# TIMER_ARDUINO_NPN.net
KiCad netlist of a schematic drawn in EAGLE
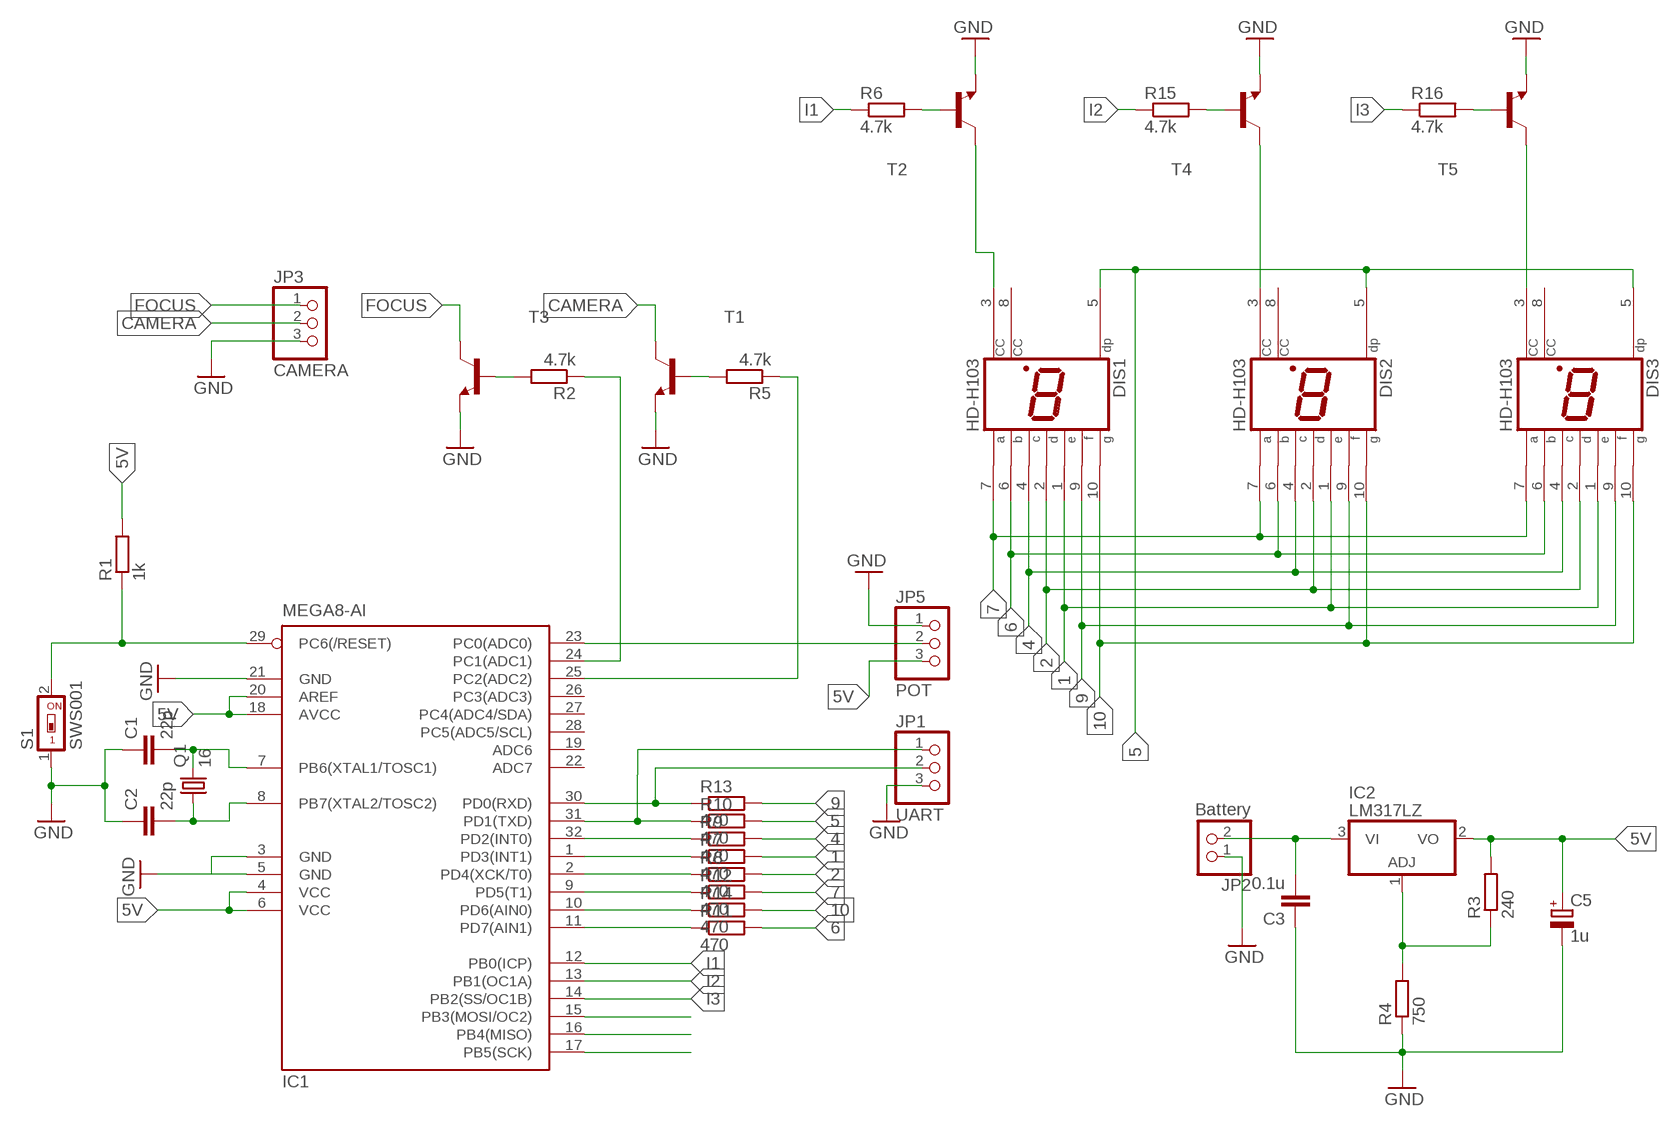
[diagram p0: schematic, sheet 1]

(export (version "E")
  (design (tool "Eeschema 10.0.6"))
  (components
    (comp (ref "C1")
      (value "22p")
      (footprint "eagle-import:C0805")
      (libsource (lib "eagle-import") (part "C-EUC0805"))
    )
    (comp (ref "C2")
      (value "22p")
      (footprint "eagle-import:C0805")
      (libsource (lib "eagle-import") (part "C-EUC0805"))
    )
    (comp (ref "C3")
      (value "0.1u")
      (footprint "eagle-import:C0805")
      (libsource (lib "eagle-import") (part "C-EUC0805"))
    )
    (comp (ref "C5")
      (value "1u")
      (footprint "eagle-import:153CLV-0405")
      (libsource (lib "eagle-import") (part "CPOL-EU153CLV-0405"))
    )
    (comp (ref "DIS1")
      (value "HD-H103")
      (footprint "eagle-import:HDSP-M")
      (libsource (lib "eagle-import") (part "HD-H103"))
    )
    (comp (ref "DIS2")
      (value "HD-H103")
      (footprint "eagle-import:HDSP-M")
      (libsource (lib "eagle-import") (part "HD-H103"))
    )
    (comp (ref "DIS3")
      (value "HD-H103")
      (footprint "eagle-import:HDSP-M")
      (libsource (lib "eagle-import") (part "HD-H103"))
    )
    (comp (ref "IC1")
      (value "MEGA8-AI")
      (footprint "eagle-import:TQFP32-08")
      (fields (field (name "MPN") "ATMEGA8-16AU"))
      (libsource (lib "eagle-import") (part "MEGA8-AI"))
    )
    (comp (ref "IC2")
      (value "LM317LZ")
      (footprint "eagle-import:TO92")
      (libsource (lib "eagle-import") (part "317LZLM"))
    )
    (comp (ref "JP1")
      (value "UART")
      (footprint "eagle-import:1X03")
      (libsource (lib "eagle-import") (part "PINHD-1X3"))
    )
    (comp (ref "JP2")
      (value "Battery")
      (footprint "eagle-import:1X02")
      (libsource (lib "eagle-import") (part "PINHD-1X2"))
    )
    (comp (ref "JP3")
      (value "CAMERA")
      (footprint "eagle-import:1X03")
      (libsource (lib "eagle-import") (part "PINHD-1X3"))
    )
    (comp (ref "JP5")
      (value "POT")
      (footprint "eagle-import:1X03")
      (libsource (lib "eagle-import") (part "PINHD-1X3"))
    )
    (comp (ref "Q1")
      (value "16")
      (footprint "eagle-import:HC33U-V")
      (libsource (lib "eagle-import") (part "CRYSTALHC33U-V"))
    )
    (comp (ref "R1")
      (value "1k")
      (footprint "eagle-import:R1206")
      (libsource (lib "eagle-import") (part "R-EU_R1206"))
    )
    (comp (ref "R2")
      (value "4.7k")
      (footprint "eagle-import:R0805")
      (libsource (lib "eagle-import") (part "R-EU_R0805"))
    )
    (comp (ref "R3")
      (value "240")
      (footprint "eagle-import:R0805")
      (libsource (lib "eagle-import") (part "R-EU_R0805"))
    )
    (comp (ref "R4")
      (value "750")
      (footprint "eagle-import:R0805")
      (libsource (lib "eagle-import") (part "R-EU_R0805"))
    )
    (comp (ref "R5")
      (value "4.7k")
      (footprint "eagle-import:R0805")
      (libsource (lib "eagle-import") (part "R-EU_R0805"))
    )
    (comp (ref "R6")
      (value "4.7k")
      (footprint "eagle-import:R0805")
      (libsource (lib "eagle-import") (part "R-EU_R0805"))
    )
    (comp (ref "R7")
      (value "470")
      (footprint "eagle-import:R0805")
      (libsource (lib "eagle-import") (part "R-EU_R0805"))
    )
    (comp (ref "R8")
      (value "470")
      (footprint "eagle-import:R0805")
      (libsource (lib "eagle-import") (part "R-EU_R0805"))
    )
    (comp (ref "R9")
      (value "470")
      (footprint "eagle-import:R0805")
      (libsource (lib "eagle-import") (part "R-EU_R0805"))
    )
    (comp (ref "R10")
      (value "470")
      (footprint "eagle-import:R0805")
      (libsource (lib "eagle-import") (part "R-EU_R0805"))
    )
    (comp (ref "R11")
      (value "470")
      (footprint "eagle-import:R0805")
      (libsource (lib "eagle-import") (part "R-EU_R0805"))
    )
    (comp (ref "R12")
      (value "470")
      (footprint "eagle-import:R0805")
      (libsource (lib "eagle-import") (part "R-EU_R0805"))
    )
    (comp (ref "R13")
      (value "470")
      (footprint "eagle-import:R0805")
      (libsource (lib "eagle-import") (part "R-EU_R0805"))
    )
    (comp (ref "R14")
      (value "470")
      (footprint "eagle-import:R0805")
      (libsource (lib "eagle-import") (part "R-EU_R0805"))
    )
    (comp (ref "R15")
      (value "4.7k")
      (footprint "eagle-import:R0805")
      (libsource (lib "eagle-import") (part "R-EU_R0805"))
    )
    (comp (ref "R16")
      (value "4.7k")
      (footprint "eagle-import:R0805")
      (libsource (lib "eagle-import") (part "R-EU_R0805"))
    )
    (comp (ref "S1")
      (value "SWS001")
      (footprint "eagle-import:SMS-001")
      (libsource (lib "eagle-import") (part "SWS001"))
    )
    (comp (ref "T1")
      (value "BC846B-NPN-SOT23-BEC")
      (footprint "eagle-import:SOT23-BEC")
      (libsource (lib "eagle-import") (part "-NPN-SOT23-BECBC846B"))
    )
    (comp (ref "T2")
      (value "BC846B-NPN-SOT23-BEC")
      (footprint "eagle-import:SOT23-BEC")
      (libsource (lib "eagle-import") (part "-NPN-SOT23-BECBC846B"))
    )
    (comp (ref "T3")
      (value "BC846B-NPN-SOT23-BEC")
      (footprint "eagle-import:SOT23-BEC")
      (libsource (lib "eagle-import") (part "-NPN-SOT23-BECBC846B"))
    )
    (comp (ref "T4")
      (value "BC846B-NPN-SOT23-BEC")
      (footprint "eagle-import:SOT23-BEC")
      (libsource (lib "eagle-import") (part "-NPN-SOT23-BECBC846B"))
    )
    (comp (ref "T5")
      (value "BC846B-NPN-SOT23-BEC")
      (footprint "eagle-import:SOT23-BEC")
      (libsource (lib "eagle-import") (part "-NPN-SOT23-BECBC846B"))
    )
  )
  (nets
    (net (code "1") (name "1") (class "Default")
      (node (ref "DIS1") (pin "1") (pinfunction "E_1") (pintype "passive"))
      (node (ref "DIS2") (pin "1") (pinfunction "E_1") (pintype "passive"))
      (node (ref "DIS3") (pin "1") (pinfunction "E_1") (pintype "passive"))
      (node (ref "R7") (pin "2") (pinfunction "2_2") (pintype "passive"))
    )
    (net (code "2") (name "2") (class "Default")
      (node (ref "DIS1") (pin "2") (pinfunction "D_2") (pintype "passive"))
      (node (ref "DIS2") (pin "2") (pinfunction "D_2") (pintype "passive"))
      (node (ref "DIS3") (pin "2") (pinfunction "D_2") (pintype "passive"))
      (node (ref "R8") (pin "2") (pinfunction "2_2") (pintype "passive"))
    )
    (net (code "3") (name "4") (class "Default")
      (node (ref "DIS1") (pin "4") (pinfunction "C_4") (pintype "passive"))
      (node (ref "DIS2") (pin "4") (pinfunction "C_4") (pintype "passive"))
      (node (ref "DIS3") (pin "4") (pinfunction "C_4") (pintype "passive"))
      (node (ref "R9") (pin "2") (pinfunction "2_2") (pintype "passive"))
    )
    (net (code "4") (name "5") (class "Default")
      (node (ref "DIS1") (pin "5") (pinfunction "DP_5") (pintype "passive"))
      (node (ref "DIS2") (pin "5") (pinfunction "DP_5") (pintype "passive"))
      (node (ref "DIS3") (pin "5") (pinfunction "DP_5") (pintype "passive"))
      (node (ref "R10") (pin "2") (pinfunction "2_2") (pintype "passive"))
    )
    (net (code "5") (name "5V") (class "Default")
      (node (ref "C5") (pin "+") (pinfunction "+_+") (pintype "passive"))
      (node (ref "IC1") (pin "18") (pinfunction "AVCC_18") (pintype "power_in"))
      (node (ref "IC1") (pin "20") (pinfunction "AREF_20") (pintype "passive"))
      (node (ref "IC1") (pin "4") (pinfunction "VCC_4") (pintype "power_in"))
      (node (ref "IC1") (pin "6") (pinfunction "VCC_6") (pintype "power_in"))
      (node (ref "IC2") (pin "2") (pinfunction "VO_2") (pintype "passive"))
      (node (ref "JP5") (pin "3") (pinfunction "3_3") (pintype "passive"))
      (node (ref "R1") (pin "2") (pinfunction "2_2") (pintype "passive"))
      (node (ref "R3") (pin "2") (pinfunction "2_2") (pintype "passive"))
    )
    (net (code "6") (name "6") (class "Default")
      (node (ref "DIS1") (pin "6") (pinfunction "B_6") (pintype "passive"))
      (node (ref "DIS2") (pin "6") (pinfunction "B_6") (pintype "passive"))
      (node (ref "DIS3") (pin "6") (pinfunction "B_6") (pintype "passive"))
      (node (ref "R11") (pin "2") (pinfunction "2_2") (pintype "passive"))
    )
    (net (code "7") (name "7") (class "Default")
      (node (ref "DIS1") (pin "7") (pinfunction "A_7") (pintype "passive"))
      (node (ref "DIS2") (pin "7") (pinfunction "A_7") (pintype "passive"))
      (node (ref "DIS3") (pin "7") (pinfunction "A_7") (pintype "passive"))
      (node (ref "R12") (pin "2") (pinfunction "2_2") (pintype "passive"))
    )
    (net (code "8") (name "9") (class "Default")
      (node (ref "DIS1") (pin "9") (pinfunction "F_9") (pintype "passive"))
      (node (ref "DIS2") (pin "9") (pinfunction "F_9") (pintype "passive"))
      (node (ref "DIS3") (pin "9") (pinfunction "F_9") (pintype "passive"))
      (node (ref "R13") (pin "2") (pinfunction "2_2") (pintype "passive"))
    )
    (net (code "9") (name "10") (class "Default")
      (node (ref "DIS1") (pin "10") (pinfunction "G_10") (pintype "passive"))
      (node (ref "DIS2") (pin "10") (pinfunction "G_10") (pintype "passive"))
      (node (ref "DIS3") (pin "10") (pinfunction "G_10") (pintype "passive"))
      (node (ref "R14") (pin "2") (pinfunction "2_2") (pintype "passive"))
    )
    (net (code "10") (name "CAMERA") (class "Default")
      (node (ref "JP3") (pin "2") (pinfunction "2_2") (pintype "passive"))
      (node (ref "T1") (pin "C") (pinfunction "C_C") (pintype "passive"))
    )
    (net (code "11") (name "FOCUS") (class "Default")
      (node (ref "JP3") (pin "1") (pinfunction "1_1") (pintype "passive"))
      (node (ref "T3") (pin "C") (pinfunction "C_C") (pintype "passive"))
    )
    (net (code "12") (name "GND") (class "Default")
      (node (ref "C1") (pin "1") (pinfunction "1_1") (pintype "passive"))
      (node (ref "C2") (pin "1") (pinfunction "1_1") (pintype "passive"))
      (node (ref "C3") (pin "1") (pinfunction "1_1") (pintype "passive"))
      (node (ref "C5") (pin "-") (pinfunction "-_-") (pintype "passive"))
      (node (ref "IC1") (pin "21") (pinfunction "GND_21") (pintype "power_in"))
      (node (ref "IC1") (pin "5") (pinfunction "GND_5") (pintype "power_in"))
      (node (ref "JP1") (pin "3") (pinfunction "3_3") (pintype "passive"))
      (node (ref "JP2") (pin "1") (pinfunction "1_1") (pintype "passive"))
      (node (ref "JP3") (pin "3") (pinfunction "3_3") (pintype "passive"))
      (node (ref "JP5") (pin "1") (pinfunction "1_1") (pintype "passive"))
      (node (ref "R4") (pin "1") (pinfunction "1_1") (pintype "passive"))
      (node (ref "S1") (pin "1") (pinfunction "1_1") (pintype "passive"))
      (node (ref "T1") (pin "E") (pinfunction "E_E") (pintype "passive"))
      (node (ref "T2") (pin "E") (pinfunction "E_E") (pintype "passive"))
      (node (ref "T3") (pin "E") (pinfunction "E_E") (pintype "passive"))
      (node (ref "T4") (pin "E") (pinfunction "E_E") (pintype "passive"))
      (node (ref "T5") (pin "E") (pinfunction "E_E") (pintype "passive"))
    )
    (net (code "13") (name "I1") (class "Default")
      (node (ref "IC1") (pin "12") (pinfunction "PB0(ICP)_12") (pintype "bidirectional"))
      (node (ref "R6") (pin "1") (pinfunction "1_1") (pintype "passive"))
    )
    (net (code "14") (name "I2") (class "Default")
      (node (ref "IC1") (pin "13") (pinfunction "PB1(OC1A)_13") (pintype "bidirectional"))
      (node (ref "R15") (pin "1") (pinfunction "1_1") (pintype "passive"))
    )
    (net (code "15") (name "I3") (class "Default")
      (node (ref "IC1") (pin "14") (pinfunction "PB2(SS/OC1B)_14") (pintype "bidirectional"))
      (node (ref "R16") (pin "1") (pinfunction "1_1") (pintype "passive"))
    )
    (net (code "16") (name "Net-(DIS1-CC-Pad3)") (class "Default")
      (node (ref "DIS1") (pin "3") (pinfunction "CC_3") (pintype "passive"))
      (node (ref "T2") (pin "C") (pinfunction "C_C") (pintype "passive"))
    )
    (net (code "17") (name "Net-(DIS2-CC-Pad3)") (class "Default")
      (node (ref "DIS2") (pin "3") (pinfunction "CC_3") (pintype "passive"))
      (node (ref "T4") (pin "C") (pinfunction "C_C") (pintype "passive"))
    )
    (net (code "18") (name "Net-(DIS3-CC-Pad3)") (class "Default")
      (node (ref "DIS3") (pin "3") (pinfunction "CC_3") (pintype "passive"))
      (node (ref "T5") (pin "C") (pinfunction "C_C") (pintype "passive"))
    )
    (net (code "19") (name "Net-(IC1-PB6(XTAL1{slash}TOSC1))") (class "Default")
      (node (ref "C1") (pin "2") (pinfunction "2_2") (pintype "passive"))
      (node (ref "IC1") (pin "7") (pinfunction "PB6(XTAL1/TOSC1)_7") (pintype "bidirectional"))
      (node (ref "Q1") (pin "2") (pinfunction "2_2") (pintype "passive"))
    )
    (net (code "20") (name "Net-(IC1-PB7(XTAL2{slash}TOSC2))") (class "Default")
      (node (ref "C2") (pin "2") (pinfunction "2_2") (pintype "passive"))
      (node (ref "IC1") (pin "8") (pinfunction "PB7(XTAL2/TOSC2)_8") (pintype "bidirectional"))
      (node (ref "Q1") (pin "1") (pinfunction "1_1") (pintype "passive"))
    )
    (net (code "21") (name "Net-(IC1-PC0(ADC0))") (class "Default")
      (node (ref "IC1") (pin "23") (pinfunction "PC0(ADC0)_23") (pintype "bidirectional"))
      (node (ref "JP5") (pin "2") (pinfunction "2_2") (pintype "passive"))
    )
    (net (code "22") (name "Net-(IC1-PC1(ADC1))") (class "Default")
      (node (ref "IC1") (pin "24") (pinfunction "PC1(ADC1)_24") (pintype "bidirectional"))
      (node (ref "R2") (pin "1") (pinfunction "1_1") (pintype "passive"))
    )
    (net (code "23") (name "Net-(IC1-PC2(ADC2))") (class "Default")
      (node (ref "IC1") (pin "25") (pinfunction "PC2(ADC2)_25") (pintype "bidirectional"))
      (node (ref "R5") (pin "1") (pinfunction "1_1") (pintype "passive"))
    )
    (net (code "24") (name "Net-(IC1-PC6({slash}RESET))") (class "Default")
      (node (ref "IC1") (pin "29") (pinfunction "PC6(/RESET)_29") (pintype "bidirectional"))
      (node (ref "R1") (pin "1") (pinfunction "1_1") (pintype "passive"))
      (node (ref "S1") (pin "2") (pinfunction "2_2") (pintype "passive"))
    )
    (net (code "25") (name "Net-(IC1-PD0(RXD))") (class "Default")
      (node (ref "IC1") (pin "30") (pinfunction "PD0(RXD)_30") (pintype "bidirectional"))
      (node (ref "JP1") (pin "2") (pinfunction "2_2") (pintype "passive"))
      (node (ref "R13") (pin "1") (pinfunction "1_1") (pintype "passive"))
    )
    (net (code "26") (name "Net-(IC1-PD1(TXD))") (class "Default")
      (node (ref "IC1") (pin "31") (pinfunction "PD1(TXD)_31") (pintype "bidirectional"))
      (node (ref "JP1") (pin "1") (pinfunction "1_1") (pintype "passive"))
      (node (ref "R10") (pin "1") (pinfunction "1_1") (pintype "passive"))
    )
    (net (code "27") (name "Net-(IC1-PD2(INT0))") (class "Default")
      (node (ref "IC1") (pin "32") (pinfunction "PD2(INT0)_32") (pintype "bidirectional"))
      (node (ref "R9") (pin "1") (pinfunction "1_1") (pintype "passive"))
    )
    (net (code "28") (name "Net-(IC1-PD3(INT1))") (class "Default")
      (node (ref "IC1") (pin "1") (pinfunction "PD3(INT1)_1") (pintype "bidirectional"))
      (node (ref "R7") (pin "1") (pinfunction "1_1") (pintype "passive"))
    )
    (net (code "29") (name "Net-(IC1-PD4(XCK{slash}T0))") (class "Default")
      (node (ref "IC1") (pin "2") (pinfunction "PD4(XCK/T0)_2") (pintype "bidirectional"))
      (node (ref "R8") (pin "1") (pinfunction "1_1") (pintype "passive"))
    )
    (net (code "30") (name "Net-(IC1-PD5(T1))") (class "Default")
      (node (ref "IC1") (pin "9") (pinfunction "PD5(T1)_9") (pintype "bidirectional"))
      (node (ref "R12") (pin "1") (pinfunction "1_1") (pintype "passive"))
    )
    (net (code "31") (name "Net-(IC1-PD6(AIN0))") (class "Default")
      (node (ref "IC1") (pin "10") (pinfunction "PD6(AIN0)_10") (pintype "bidirectional"))
      (node (ref "R14") (pin "1") (pinfunction "1_1") (pintype "passive"))
    )
    (net (code "32") (name "Net-(IC1-PD7(AIN1))") (class "Default")
      (node (ref "IC1") (pin "11") (pinfunction "PD7(AIN1)_11") (pintype "bidirectional"))
      (node (ref "R11") (pin "1") (pinfunction "1_1") (pintype "passive"))
    )
    (net (code "33") (name "Net-(IC2-ADJ)") (class "Default")
      (node (ref "IC2") (pin "1") (pinfunction "ADJ_1") (pintype "input"))
      (node (ref "R3") (pin "1") (pinfunction "1_1") (pintype "passive"))
      (node (ref "R4") (pin "2") (pinfunction "2_2") (pintype "passive"))
    )
    (net (code "34") (name "Net-(IC2-VI)") (class "Default")
      (node (ref "C3") (pin "2") (pinfunction "2_2") (pintype "passive"))
      (node (ref "IC2") (pin "3") (pinfunction "VI_3") (pintype "input"))
      (node (ref "JP2") (pin "2") (pinfunction "2_2") (pintype "passive"))
    )
    (net (code "35") (name "Net-(R2-Pad2)") (class "Default")
      (node (ref "R2") (pin "2") (pinfunction "2_2") (pintype "passive"))
      (node (ref "T3") (pin "B") (pinfunction "B_B") (pintype "passive"))
    )
    (net (code "36") (name "Net-(R5-Pad2)") (class "Default")
      (node (ref "R5") (pin "2") (pinfunction "2_2") (pintype "passive"))
      (node (ref "T1") (pin "B") (pinfunction "B_B") (pintype "passive"))
    )
    (net (code "37") (name "Net-(R6-Pad2)") (class "Default")
      (node (ref "R6") (pin "2") (pinfunction "2_2") (pintype "passive"))
      (node (ref "T2") (pin "B") (pinfunction "B_B") (pintype "passive"))
    )
    (net (code "38") (name "Net-(R15-Pad2)") (class "Default")
      (node (ref "R15") (pin "2") (pinfunction "2_2") (pintype "passive"))
      (node (ref "T4") (pin "B") (pinfunction "B_B") (pintype "passive"))
    )
    (net (code "39") (name "Net-(R16-Pad2)") (class "Default")
      (node (ref "R16") (pin "2") (pinfunction "2_2") (pintype "passive"))
      (node (ref "T5") (pin "B") (pinfunction "B_B") (pintype "passive"))
    )
    (net (code "40") (name "unconnected-(DIS1-CC-Pad8)") (class "Default")
      (node (ref "DIS1") (pin "8") (pinfunction "CC_8") (pintype "passive"))
    )
    (net (code "41") (name "unconnected-(DIS2-CC-Pad8)") (class "Default")
      (node (ref "DIS2") (pin "8") (pinfunction "CC_8") (pintype "passive"))
    )
    (net (code "42") (name "unconnected-(DIS3-CC-Pad8)") (class "Default")
      (node (ref "DIS3") (pin "8") (pinfunction "CC_8") (pintype "passive"))
    )
    (net (code "43") (name "unconnected-(IC1-ADC6-Pad19)") (class "Default")
      (node (ref "IC1") (pin "19") (pinfunction "ADC6_19") (pintype "bidirectional"))
    )
    (net (code "44") (name "unconnected-(IC1-ADC7-Pad22)") (class "Default")
      (node (ref "IC1") (pin "22") (pinfunction "ADC7_22") (pintype "bidirectional"))
    )
    (net (code "45") (name "unconnected-(IC1-GND-Pad3)") (class "Default")
      (node (ref "IC1") (pin "3") (pinfunction "GND_3") (pintype "power_in"))
    )
    (net (code "46") (name "unconnected-(IC1-PB3(MOSI{slash}OC2)-Pad15)") (class "Default")
      (node (ref "IC1") (pin "15") (pinfunction "PB3(MOSI/OC2)_15") (pintype "bidirectional"))
    )
    (net (code "47") (name "unconnected-(IC1-PB4(MISO)-Pad16)") (class "Default")
      (node (ref "IC1") (pin "16") (pinfunction "PB4(MISO)_16") (pintype "bidirectional"))
    )
    (net (code "48") (name "unconnected-(IC1-PB5(SCK)-Pad17)") (class "Default")
      (node (ref "IC1") (pin "17") (pinfunction "PB5(SCK)_17") (pintype "bidirectional"))
    )
    (net (code "49") (name "unconnected-(IC1-PC3(ADC3)-Pad26)") (class "Default")
      (node (ref "IC1") (pin "26") (pinfunction "PC3(ADC3)_26") (pintype "bidirectional"))
    )
    (net (code "50") (name "unconnected-(IC1-PC4(ADC4{slash}SDA)-Pad27)") (class "Default")
      (node (ref "IC1") (pin "27") (pinfunction "PC4(ADC4/SDA)_27") (pintype "bidirectional"))
    )
    (net (code "51") (name "unconnected-(IC1-PC5(ADC5{slash}SCL)-Pad28)") (class "Default")
      (node (ref "IC1") (pin "28") (pinfunction "PC5(ADC5/SCL)_28") (pintype "bidirectional"))
    )
  )
)
